# 03_Connectors.net
KiCad netlist of a schematic drawn in Altium Designer
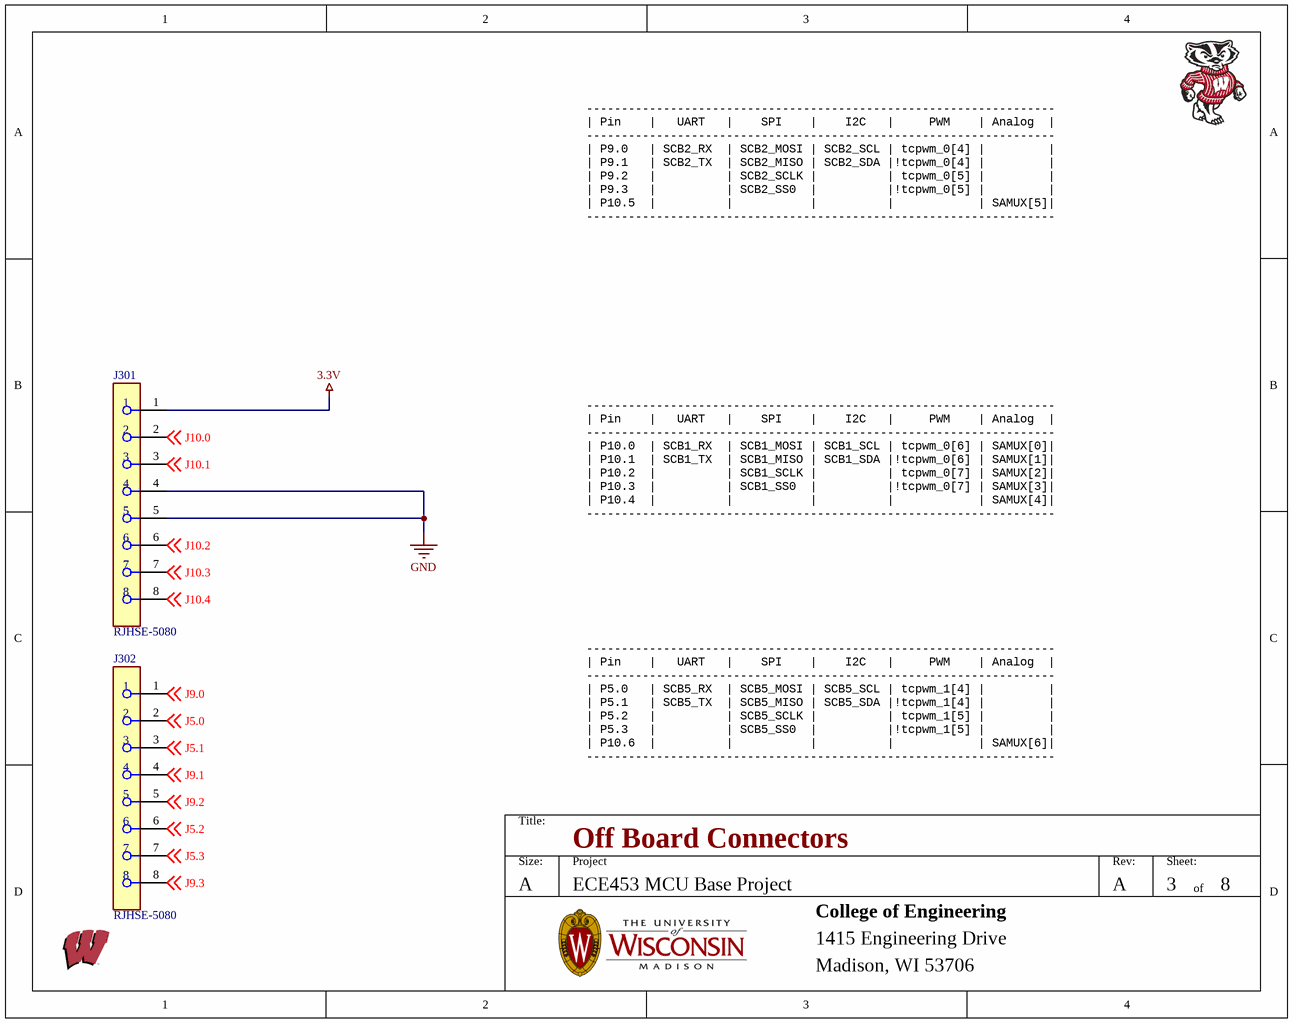
[diagram p0: 03_Connectors.SchDoc]

(export (version "E")
  (design (tool "Eeschema 10.0.6"))
  (components
    (comp (ref "J301")
      (value "RJHSE-5080")
      (footprint "FP-RJHSE-5080-MFG")
      (description "CONN MOD JACK 8P8C R/A UNSHLD")
      (fields
        (field (name "OCTOPART") "https://octopart.com/rjhse-5080-amphenol-45060")
        (field (name "MANUFACTURER") "Amphenol")
      )
      (libsource (lib "Altium Content Vault") (part "b0a0b555dd3abf3683e7c330df25cc4"))
    )
    (comp (ref "J302")
      (value "RJHSE-5080")
      (footprint "FP-RJHSE-5080-MFG")
      (description "CONN MOD JACK 8P8C R/A UNSHLD")
      (fields
        (field (name "OCTOPART") "https://octopart.com/rjhse-5080-amphenol-45060")
        (field (name "MANUFACTURER") "Amphenol")
      )
      (libsource (lib "Altium Content Vault") (part "b0a0b555dd3abf3683e7c330df25cc4"))
    )
  )
  (nets
    (net (code "1") (name "3.3V") (class "Default")
      (node (ref "J301") (pin "1") (pinfunction "1_1") (pintype "passive"))
    )
    (net (code "2") (name "GND") (class "Default")
      (node (ref "J301") (pin "4") (pinfunction "4_4") (pintype "passive"))
      (node (ref "J301") (pin "5") (pinfunction "5_5") (pintype "passive"))
    )
    (net (code "3") (name "J5.0") (class "Default")
      (node (ref "J302") (pin "2") (pinfunction "2_2") (pintype "passive"))
    )
    (net (code "4") (name "J5.1") (class "Default")
      (node (ref "J302") (pin "3") (pinfunction "3_3") (pintype "passive"))
    )
    (net (code "5") (name "J5.2") (class "Default")
      (node (ref "J302") (pin "6") (pinfunction "6_6") (pintype "passive"))
    )
    (net (code "6") (name "J5.3") (class "Default")
      (node (ref "J302") (pin "7") (pinfunction "7_7") (pintype "passive"))
    )
    (net (code "7") (name "J9.0") (class "Default")
      (node (ref "J302") (pin "1") (pinfunction "1_1") (pintype "passive"))
    )
    (net (code "8") (name "J9.1") (class "Default")
      (node (ref "J302") (pin "4") (pinfunction "4_4") (pintype "passive"))
    )
    (net (code "9") (name "J9.2") (class "Default")
      (node (ref "J302") (pin "5") (pinfunction "5_5") (pintype "passive"))
    )
    (net (code "10") (name "J9.3") (class "Default")
      (node (ref "J302") (pin "8") (pinfunction "8_8") (pintype "passive"))
    )
    (net (code "11") (name "J10.0") (class "Default")
      (node (ref "J301") (pin "2") (pinfunction "2_2") (pintype "passive"))
    )
    (net (code "12") (name "J10.1") (class "Default")
      (node (ref "J301") (pin "3") (pinfunction "3_3") (pintype "passive"))
    )
    (net (code "13") (name "J10.2") (class "Default")
      (node (ref "J301") (pin "6") (pinfunction "6_6") (pintype "passive"))
    )
    (net (code "14") (name "J10.3") (class "Default")
      (node (ref "J301") (pin "7") (pinfunction "7_7") (pintype "passive"))
    )
    (net (code "15") (name "J10.4") (class "Default")
      (node (ref "J301") (pin "8") (pinfunction "8_8") (pintype "passive"))
    )
  )
)
